# HSHV4-student_versionTester.net
KiCad netlist of a schematic drawn in EAGLE
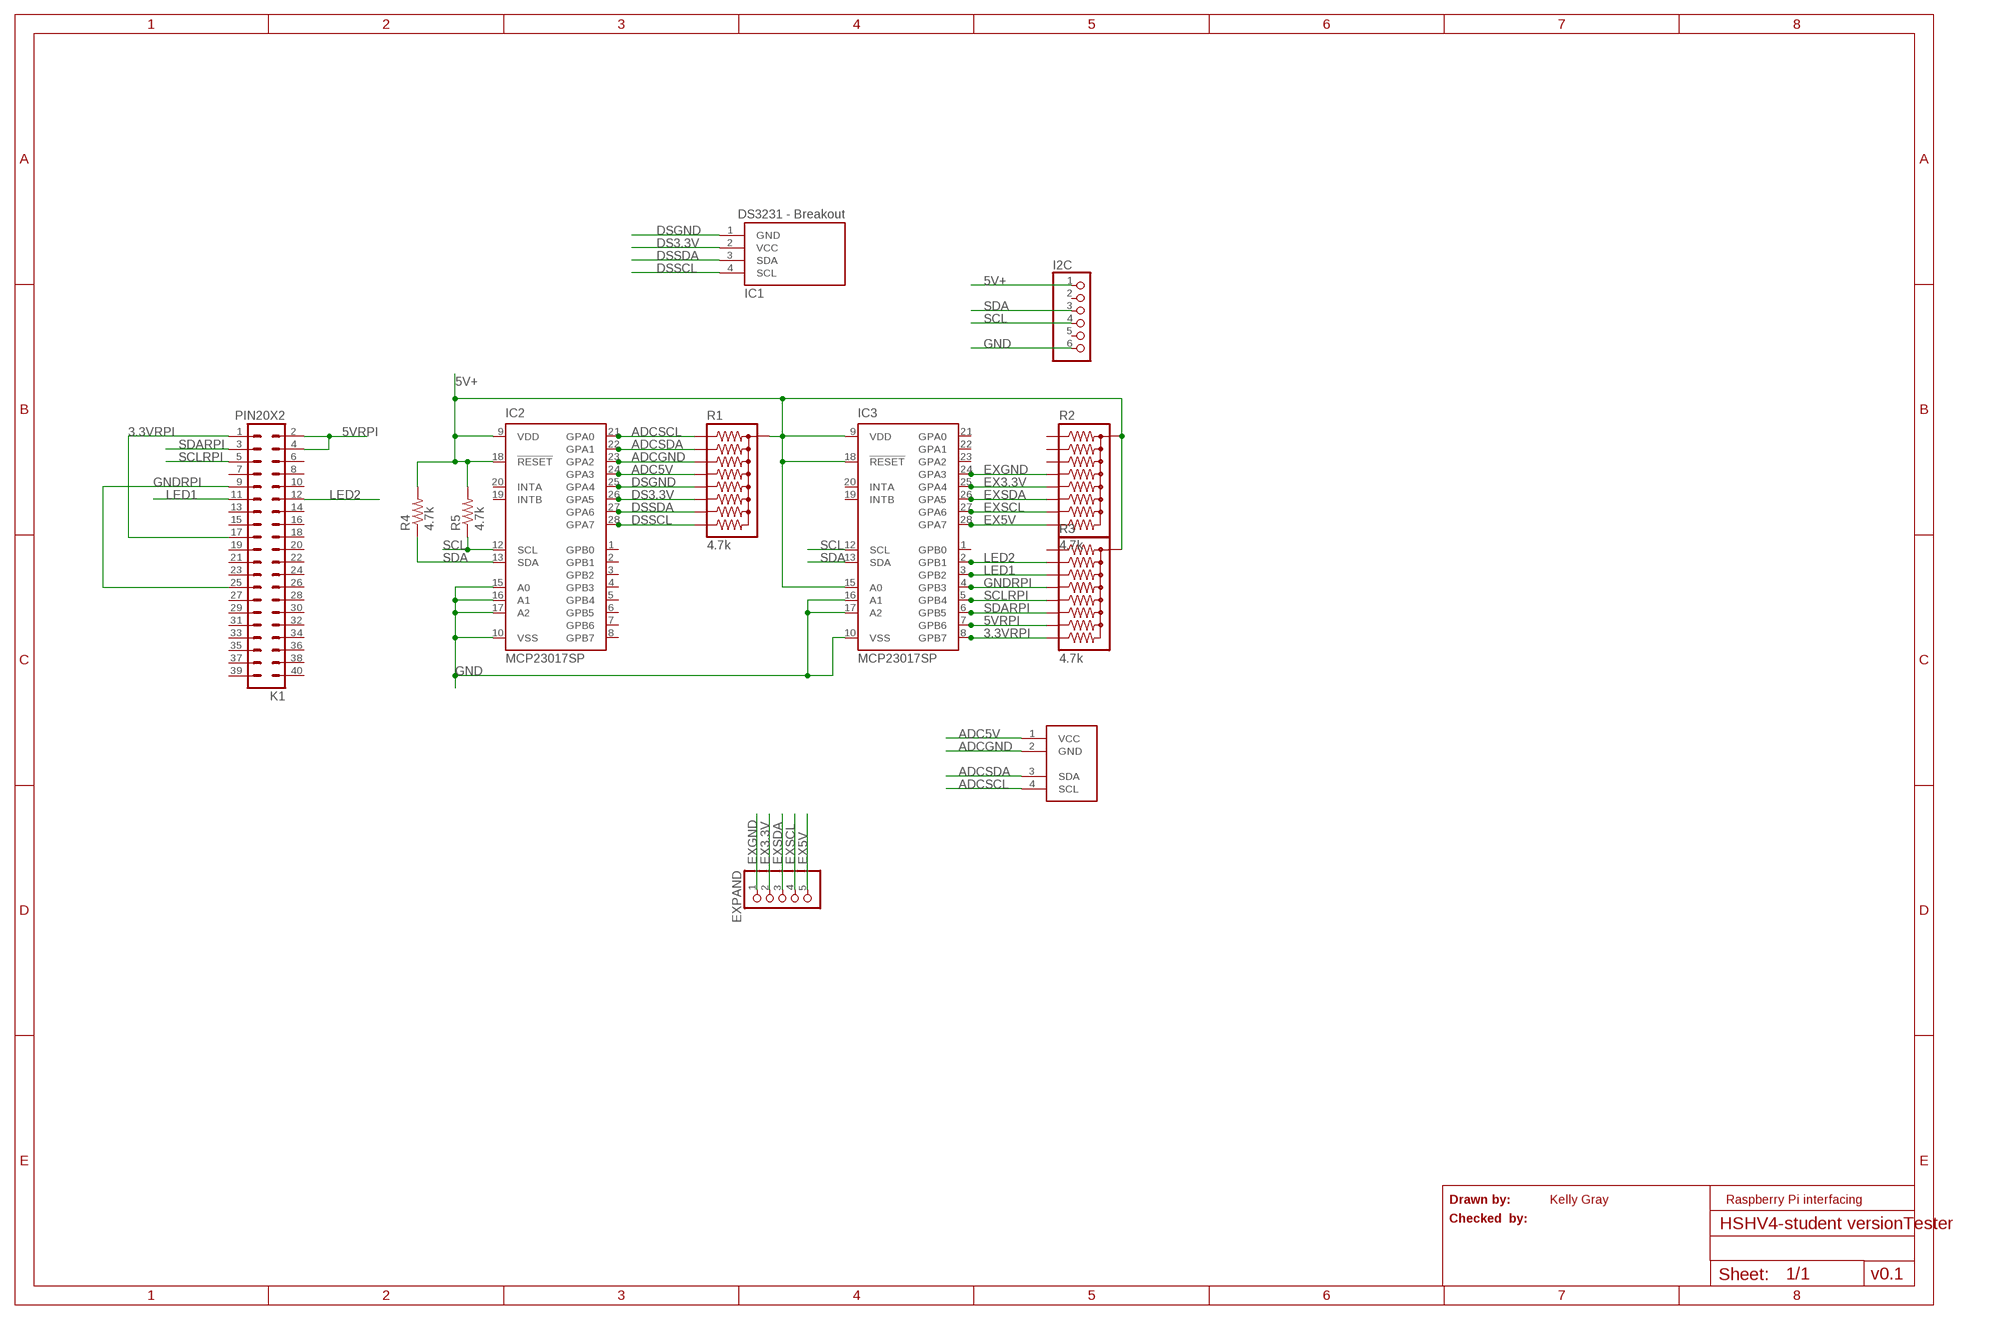
[diagram p0: schematic, sheet 1]

(export (version "E")
  (design (tool "Eeschema 10.0.6"))
  (components
    (comp (ref "EXPAND")
      (value "PINHD-1X5")
      (footprint "eagle-import:1X05")
      (libsource (lib "eagle-import") (part "PINHD-1X5"))
    )
    (comp (ref "I2C")
      (value "PINHD-1X6")
      (footprint "eagle-import:1X06")
      (libsource (lib "eagle-import") (part "PINHD-1X6"))
    )
    (comp (ref "IC1")
      (value "DS3231")
      (footprint "eagle-import:8PTH")
      (libsource (lib "eagle-import") (part "DS3231"))
    )
    (comp (ref "IC2")
      (value "MCP23017SP")
      (footprint "eagle-import:DIL28-3")
      (libsource (lib "eagle-import") (part "MCP23017SP"))
    )
    (comp (ref "IC3")
      (value "MCP23017SP")
      (footprint "eagle-import:DIL28-3")
      (libsource (lib "eagle-import") (part "MCP23017SP"))
    )
    (comp (ref "K1")
      (value "PIN20X2")
      (footprint "eagle-import:PIN_20X2")
      (libsource (lib "eagle-import") (part "PIN20X2"))
    )
    (comp (ref "R1")
      (value "4.7k")
      (footprint "eagle-import:RPACK-SIP-PTH-8")
      (libsource (lib "eagle-import") (part "RPACK-BUSSED-8-SIP-PTH-8"))
    )
    (comp (ref "R2")
      (value "4.7k")
      (footprint "eagle-import:RPACK-SIP-PTH-8")
      (libsource (lib "eagle-import") (part "RPACK-BUSSED-8-SIP-PTH-8"))
    )
    (comp (ref "R3")
      (value "4.7k")
      (footprint "eagle-import:RPACK-SIP-PTH-8")
      (libsource (lib "eagle-import") (part "RPACK-BUSSED-8-SIP-PTH-8"))
    )
    (comp (ref "R4")
      (value "4.7k")
      (footprint "eagle-import:0414_15")
      (libsource (lib "eagle-import") (part "R-US_0414/15"))
    )
    (comp (ref "R5")
      (value "4.7k")
      (footprint "eagle-import:0414_15")
      (libsource (lib "eagle-import") (part "R-US_0414/15"))
    )
    (comp (ref "U$1")
      (value "PCF8591")
      (footprint "eagle-import:1X04")
      (libsource (lib "eagle-import") (part "PCF8591"))
    )
  )
  (nets
    (net (code "1") (name "/3.3VRPI") (class "Default")
      (node (ref "IC3") (pin "8") (pinfunction "GPB7_8") (pintype "bidirectional"))
      (node (ref "K1") (pin "1") (pinfunction "1_1") (pintype "passive"))
      (node (ref "K1") (pin "17") (pinfunction "17_17") (pintype "passive"))
      (node (ref "R3") (pin "P$9") (pinfunction "9_P$9") (pintype "passive"))
    )
    (net (code "2") (name "/5V+") (class "Default")
      (node (ref "I2C") (pin "1") (pinfunction "1_1") (pintype "passive"))
      (node (ref "IC2") (pin "18") (pinfunction "~{RESET}_18") (pintype "input"))
      (node (ref "IC2") (pin "9") (pinfunction "VDD_9") (pintype "power_in"))
      (node (ref "IC3") (pin "15") (pinfunction "A0_15") (pintype "input"))
      (node (ref "IC3") (pin "18") (pinfunction "~{RESET}_18") (pintype "input"))
      (node (ref "IC3") (pin "9") (pinfunction "VDD_9") (pintype "power_in"))
      (node (ref "R1") (pin "P$1") (pinfunction "1_P$1") (pintype "passive"))
      (node (ref "R2") (pin "P$1") (pinfunction "1_P$1") (pintype "passive"))
      (node (ref "R3") (pin "P$1") (pinfunction "1_P$1") (pintype "passive"))
      (node (ref "R4") (pin "2") (pinfunction "2_2") (pintype "passive"))
      (node (ref "R5") (pin "2") (pinfunction "2_2") (pintype "passive"))
    )
    (net (code "3") (name "/5VRPI") (class "Default")
      (node (ref "IC3") (pin "7") (pinfunction "GPB6_7") (pintype "bidirectional"))
      (node (ref "K1") (pin "2") (pinfunction "2_2") (pintype "passive"))
      (node (ref "K1") (pin "4") (pinfunction "4_4") (pintype "passive"))
      (node (ref "R3") (pin "P$8") (pinfunction "8_P$8") (pintype "passive"))
    )
    (net (code "4") (name "/ADC5V") (class "Default")
      (node (ref "IC2") (pin "24") (pinfunction "GPA3_24") (pintype "bidirectional"))
      (node (ref "R1") (pin "P$5") (pinfunction "5_P$5") (pintype "passive"))
      (node (ref "U$1") (pin "1") (pinfunction "VCC_1") (pintype "bidirectional"))
    )
    (net (code "5") (name "/ADCGND") (class "Default")
      (node (ref "IC2") (pin "23") (pinfunction "GPA2_23") (pintype "bidirectional"))
      (node (ref "R1") (pin "P$4") (pinfunction "4_P$4") (pintype "passive"))
      (node (ref "U$1") (pin "2") (pinfunction "GND_2") (pintype "bidirectional"))
    )
    (net (code "6") (name "/ADCSCL") (class "Default")
      (node (ref "IC2") (pin "21") (pinfunction "GPA0_21") (pintype "bidirectional"))
      (node (ref "R1") (pin "P$2") (pinfunction "2_P$2") (pintype "passive"))
      (node (ref "U$1") (pin "4") (pinfunction "SCL_4") (pintype "bidirectional"))
    )
    (net (code "7") (name "/ADCSDA") (class "Default")
      (node (ref "IC2") (pin "22") (pinfunction "GPA1_22") (pintype "bidirectional"))
      (node (ref "R1") (pin "P$3") (pinfunction "3_P$3") (pintype "passive"))
      (node (ref "U$1") (pin "3") (pinfunction "SDA_3") (pintype "bidirectional"))
    )
    (net (code "8") (name "/DS3.3V") (class "Default")
      (node (ref "IC1") (pin "2") (pinfunction "VCC_2") (pintype "power_in"))
      (node (ref "IC2") (pin "26") (pinfunction "GPA5_26") (pintype "bidirectional"))
      (node (ref "R1") (pin "P$7") (pinfunction "7_P$7") (pintype "passive"))
    )
    (net (code "9") (name "/DSGND") (class "Default")
      (node (ref "IC1") (pin "1") (pinfunction "GND_1") (pintype "power_in"))
      (node (ref "IC2") (pin "25") (pinfunction "GPA4_25") (pintype "bidirectional"))
      (node (ref "R1") (pin "P$6") (pinfunction "6_P$6") (pintype "passive"))
    )
    (net (code "10") (name "/DSSCL") (class "Default")
      (node (ref "IC1") (pin "4") (pinfunction "SCL_4") (pintype "bidirectional"))
      (node (ref "IC2") (pin "28") (pinfunction "GPA7_28") (pintype "bidirectional"))
      (node (ref "R1") (pin "P$9") (pinfunction "9_P$9") (pintype "passive"))
    )
    (net (code "11") (name "/DSSDA") (class "Default")
      (node (ref "IC1") (pin "3") (pinfunction "SDA_3") (pintype "bidirectional"))
      (node (ref "IC2") (pin "27") (pinfunction "GPA6_27") (pintype "bidirectional"))
      (node (ref "R1") (pin "P$8") (pinfunction "8_P$8") (pintype "passive"))
    )
    (net (code "12") (name "/EX3.3V") (class "Default")
      (node (ref "EXPAND") (pin "2") (pinfunction "2_2") (pintype "passive"))
      (node (ref "IC3") (pin "25") (pinfunction "GPA4_25") (pintype "bidirectional"))
      (node (ref "R2") (pin "P$6") (pinfunction "6_P$6") (pintype "passive"))
    )
    (net (code "13") (name "/EX5V") (class "Default")
      (node (ref "EXPAND") (pin "5") (pinfunction "5_5") (pintype "passive"))
      (node (ref "IC3") (pin "28") (pinfunction "GPA7_28") (pintype "bidirectional"))
      (node (ref "R2") (pin "P$9") (pinfunction "9_P$9") (pintype "passive"))
    )
    (net (code "14") (name "/EXGND") (class "Default")
      (node (ref "EXPAND") (pin "1") (pinfunction "1_1") (pintype "passive"))
      (node (ref "IC3") (pin "24") (pinfunction "GPA3_24") (pintype "bidirectional"))
      (node (ref "R2") (pin "P$5") (pinfunction "5_P$5") (pintype "passive"))
    )
    (net (code "15") (name "/EXSCL") (class "Default")
      (node (ref "EXPAND") (pin "4") (pinfunction "4_4") (pintype "passive"))
      (node (ref "IC3") (pin "27") (pinfunction "GPA6_27") (pintype "bidirectional"))
      (node (ref "R2") (pin "P$8") (pinfunction "8_P$8") (pintype "passive"))
    )
    (net (code "16") (name "/EXSDA") (class "Default")
      (node (ref "EXPAND") (pin "3") (pinfunction "3_3") (pintype "passive"))
      (node (ref "IC3") (pin "26") (pinfunction "GPA5_26") (pintype "bidirectional"))
      (node (ref "R2") (pin "P$7") (pinfunction "7_P$7") (pintype "passive"))
    )
    (net (code "17") (name "/GND") (class "Default")
      (node (ref "I2C") (pin "6") (pinfunction "6_6") (pintype "passive"))
      (node (ref "IC2") (pin "10") (pinfunction "VSS_10") (pintype "power_in"))
      (node (ref "IC2") (pin "15") (pinfunction "A0_15") (pintype "input"))
      (node (ref "IC2") (pin "16") (pinfunction "A1_16") (pintype "input"))
      (node (ref "IC2") (pin "17") (pinfunction "A2_17") (pintype "input"))
      (node (ref "IC3") (pin "10") (pinfunction "VSS_10") (pintype "power_in"))
      (node (ref "IC3") (pin "16") (pinfunction "A1_16") (pintype "input"))
      (node (ref "IC3") (pin "17") (pinfunction "A2_17") (pintype "input"))
    )
    (net (code "18") (name "/GNDRPI") (class "Default")
      (node (ref "IC3") (pin "4") (pinfunction "GPB3_4") (pintype "bidirectional"))
      (node (ref "K1") (pin "25") (pinfunction "25_25") (pintype "passive"))
      (node (ref "K1") (pin "9") (pinfunction "9_9") (pintype "passive"))
      (node (ref "R3") (pin "P$5") (pinfunction "5_P$5") (pintype "passive"))
    )
    (net (code "19") (name "/LED1") (class "Default")
      (node (ref "IC3") (pin "3") (pinfunction "GPB2_3") (pintype "bidirectional"))
      (node (ref "K1") (pin "11") (pinfunction "11_11") (pintype "passive"))
      (node (ref "R3") (pin "P$4") (pinfunction "4_P$4") (pintype "passive"))
    )
    (net (code "20") (name "/LED2") (class "Default")
      (node (ref "IC3") (pin "2") (pinfunction "GPB1_2") (pintype "bidirectional"))
      (node (ref "K1") (pin "12") (pinfunction "12_12") (pintype "passive"))
      (node (ref "R3") (pin "P$3") (pinfunction "3_P$3") (pintype "passive"))
    )
    (net (code "21") (name "/SCL") (class "Default")
      (node (ref "I2C") (pin "4") (pinfunction "4_4") (pintype "passive"))
      (node (ref "IC2") (pin "12") (pinfunction "SCL_12") (pintype "input"))
      (node (ref "IC3") (pin "12") (pinfunction "SCL_12") (pintype "input"))
      (node (ref "R5") (pin "1") (pinfunction "1_1") (pintype "passive"))
    )
    (net (code "22") (name "/SCLRPI") (class "Default")
      (node (ref "IC3") (pin "5") (pinfunction "GPB4_5") (pintype "bidirectional"))
      (node (ref "K1") (pin "5") (pinfunction "5_5") (pintype "passive"))
      (node (ref "R3") (pin "P$6") (pinfunction "6_P$6") (pintype "passive"))
    )
    (net (code "23") (name "/SDA") (class "Default")
      (node (ref "I2C") (pin "3") (pinfunction "3_3") (pintype "passive"))
      (node (ref "IC2") (pin "13") (pinfunction "SDA_13") (pintype "bidirectional"))
      (node (ref "IC3") (pin "13") (pinfunction "SDA_13") (pintype "bidirectional"))
      (node (ref "R4") (pin "1") (pinfunction "1_1") (pintype "passive"))
    )
    (net (code "24") (name "/SDARPI") (class "Default")
      (node (ref "IC3") (pin "6") (pinfunction "GPB5_6") (pintype "bidirectional"))
      (node (ref "K1") (pin "3") (pinfunction "3_3") (pintype "passive"))
      (node (ref "R3") (pin "P$7") (pinfunction "7_P$7") (pintype "passive"))
    )
    (net (code "25") (name "unconnected-(I2C-Pad2)") (class "Default")
      (node (ref "I2C") (pin "2") (pinfunction "2_2") (pintype "passive"))
    )
    (net (code "26") (name "unconnected-(I2C-Pad5)") (class "Default")
      (node (ref "I2C") (pin "5") (pinfunction "5_5") (pintype "passive"))
    )
    (net (code "27") (name "unconnected-(IC2-GPB0-Pad1)") (class "Default")
      (node (ref "IC2") (pin "1") (pinfunction "GPB0_1") (pintype "bidirectional"))
    )
    (net (code "28") (name "unconnected-(IC2-GPB1-Pad2)") (class "Default")
      (node (ref "IC2") (pin "2") (pinfunction "GPB1_2") (pintype "bidirectional"))
    )
    (net (code "29") (name "unconnected-(IC2-GPB2-Pad3)") (class "Default")
      (node (ref "IC2") (pin "3") (pinfunction "GPB2_3") (pintype "bidirectional"))
    )
    (net (code "30") (name "unconnected-(IC2-GPB3-Pad4)") (class "Default")
      (node (ref "IC2") (pin "4") (pinfunction "GPB3_4") (pintype "bidirectional"))
    )
    (net (code "31") (name "unconnected-(IC2-GPB4-Pad5)") (class "Default")
      (node (ref "IC2") (pin "5") (pinfunction "GPB4_5") (pintype "bidirectional"))
    )
    (net (code "32") (name "unconnected-(IC2-GPB5-Pad6)") (class "Default")
      (node (ref "IC2") (pin "6") (pinfunction "GPB5_6") (pintype "bidirectional"))
    )
    (net (code "33") (name "unconnected-(IC2-GPB6-Pad7)") (class "Default")
      (node (ref "IC2") (pin "7") (pinfunction "GPB6_7") (pintype "bidirectional"))
    )
    (net (code "34") (name "unconnected-(IC2-GPB7-Pad8)") (class "Default")
      (node (ref "IC2") (pin "8") (pinfunction "GPB7_8") (pintype "bidirectional"))
    )
    (net (code "35") (name "unconnected-(IC2-INTA-Pad20)") (class "Default")
      (node (ref "IC2") (pin "20") (pinfunction "INTA_20") (pintype "output"))
    )
    (net (code "36") (name "unconnected-(IC2-INTB-Pad19)") (class "Default")
      (node (ref "IC2") (pin "19") (pinfunction "INTB_19") (pintype "output"))
    )
    (net (code "37") (name "unconnected-(IC3-GPA0-Pad21)") (class "Default")
      (node (ref "IC3") (pin "21") (pinfunction "GPA0_21") (pintype "bidirectional"))
    )
    (net (code "38") (name "unconnected-(IC3-GPA1-Pad22)") (class "Default")
      (node (ref "IC3") (pin "22") (pinfunction "GPA1_22") (pintype "bidirectional"))
    )
    (net (code "39") (name "unconnected-(IC3-GPA2-Pad23)") (class "Default")
      (node (ref "IC3") (pin "23") (pinfunction "GPA2_23") (pintype "bidirectional"))
    )
    (net (code "40") (name "unconnected-(IC3-GPB0-Pad1)") (class "Default")
      (node (ref "IC3") (pin "1") (pinfunction "GPB0_1") (pintype "bidirectional"))
    )
    (net (code "41") (name "unconnected-(IC3-INTA-Pad20)") (class "Default")
      (node (ref "IC3") (pin "20") (pinfunction "INTA_20") (pintype "output"))
    )
    (net (code "42") (name "unconnected-(IC3-INTB-Pad19)") (class "Default")
      (node (ref "IC3") (pin "19") (pinfunction "INTB_19") (pintype "output"))
    )
    (net (code "43") (name "unconnected-(K1-Pad6)") (class "Default")
      (node (ref "K1") (pin "6") (pinfunction "6_6") (pintype "passive"))
    )
    (net (code "44") (name "unconnected-(K1-Pad7)") (class "Default")
      (node (ref "K1") (pin "7") (pinfunction "7_7") (pintype "passive"))
    )
    (net (code "45") (name "unconnected-(K1-Pad8)") (class "Default")
      (node (ref "K1") (pin "8") (pinfunction "8_8") (pintype "passive"))
    )
    (net (code "46") (name "unconnected-(K1-Pad10)") (class "Default")
      (node (ref "K1") (pin "10") (pinfunction "10_10") (pintype "passive"))
    )
    (net (code "47") (name "unconnected-(K1-Pad13)") (class "Default")
      (node (ref "K1") (pin "13") (pinfunction "13_13") (pintype "passive"))
    )
    (net (code "48") (name "unconnected-(K1-Pad14)") (class "Default")
      (node (ref "K1") (pin "14") (pinfunction "14_14") (pintype "passive"))
    )
    (net (code "49") (name "unconnected-(K1-Pad15)") (class "Default")
      (node (ref "K1") (pin "15") (pinfunction "15_15") (pintype "passive"))
    )
    (net (code "50") (name "unconnected-(K1-Pad16)") (class "Default")
      (node (ref "K1") (pin "16") (pinfunction "16_16") (pintype "passive"))
    )
    (net (code "51") (name "unconnected-(K1-Pad18)") (class "Default")
      (node (ref "K1") (pin "18") (pinfunction "18_18") (pintype "passive"))
    )
    (net (code "52") (name "unconnected-(K1-Pad19)") (class "Default")
      (node (ref "K1") (pin "19") (pinfunction "19_19") (pintype "passive"))
    )
    (net (code "53") (name "unconnected-(K1-Pad20)") (class "Default")
      (node (ref "K1") (pin "20") (pinfunction "20_20") (pintype "passive"))
    )
    (net (code "54") (name "unconnected-(K1-Pad21)") (class "Default")
      (node (ref "K1") (pin "21") (pinfunction "21_21") (pintype "passive"))
    )
    (net (code "55") (name "unconnected-(K1-Pad22)") (class "Default")
      (node (ref "K1") (pin "22") (pinfunction "22_22") (pintype "passive"))
    )
    (net (code "56") (name "unconnected-(K1-Pad23)") (class "Default")
      (node (ref "K1") (pin "23") (pinfunction "23_23") (pintype "passive"))
    )
    (net (code "57") (name "unconnected-(K1-Pad24)") (class "Default")
      (node (ref "K1") (pin "24") (pinfunction "24_24") (pintype "passive"))
    )
    (net (code "58") (name "unconnected-(K1-Pad26)") (class "Default")
      (node (ref "K1") (pin "26") (pinfunction "26_26") (pintype "passive"))
    )
    (net (code "59") (name "unconnected-(K1-Pad27)") (class "Default")
      (node (ref "K1") (pin "27") (pinfunction "27_27") (pintype "passive"))
    )
    (net (code "60") (name "unconnected-(K1-Pad28)") (class "Default")
      (node (ref "K1") (pin "28") (pinfunction "28_28") (pintype "passive"))
    )
    (net (code "61") (name "unconnected-(K1-Pad29)") (class "Default")
      (node (ref "K1") (pin "29") (pinfunction "29_29") (pintype "passive"))
    )
    (net (code "62") (name "unconnected-(K1-Pad30)") (class "Default")
      (node (ref "K1") (pin "30") (pinfunction "30_30") (pintype "passive"))
    )
    (net (code "63") (name "unconnected-(K1-Pad31)") (class "Default")
      (node (ref "K1") (pin "31") (pinfunction "31_31") (pintype "passive"))
    )
    (net (code "64") (name "unconnected-(K1-Pad32)") (class "Default")
      (node (ref "K1") (pin "32") (pinfunction "32_32") (pintype "passive"))
    )
    (net (code "65") (name "unconnected-(K1-Pad33)") (class "Default")
      (node (ref "K1") (pin "33") (pinfunction "33_33") (pintype "passive"))
    )
    (net (code "66") (name "unconnected-(K1-Pad34)") (class "Default")
      (node (ref "K1") (pin "34") (pinfunction "34_34") (pintype "passive"))
    )
    (net (code "67") (name "unconnected-(K1-Pad35)") (class "Default")
      (node (ref "K1") (pin "35") (pinfunction "35_35") (pintype "passive"))
    )
    (net (code "68") (name "unconnected-(K1-Pad36)") (class "Default")
      (node (ref "K1") (pin "36") (pinfunction "36_36") (pintype "passive"))
    )
    (net (code "69") (name "unconnected-(K1-Pad37)") (class "Default")
      (node (ref "K1") (pin "37") (pinfunction "37_37") (pintype "passive"))
    )
    (net (code "70") (name "unconnected-(K1-Pad38)") (class "Default")
      (node (ref "K1") (pin "38") (pinfunction "38_38") (pintype "passive"))
    )
    (net (code "71") (name "unconnected-(K1-Pad39)") (class "Default")
      (node (ref "K1") (pin "39") (pinfunction "39_39") (pintype "passive"))
    )
    (net (code "72") (name "unconnected-(K1-Pad40)") (class "Default")
      (node (ref "K1") (pin "40") (pinfunction "40_40") (pintype "passive"))
    )
    (net (code "73") (name "unconnected-(R2-2-PadP$2)") (class "Default")
      (node (ref "R2") (pin "P$2") (pinfunction "2_P$2") (pintype "passive"))
    )
    (net (code "74") (name "unconnected-(R2-3-PadP$3)") (class "Default")
      (node (ref "R2") (pin "P$3") (pinfunction "3_P$3") (pintype "passive"))
    )
    (net (code "75") (name "unconnected-(R2-4-PadP$4)") (class "Default")
      (node (ref "R2") (pin "P$4") (pinfunction "4_P$4") (pintype "passive"))
    )
    (net (code "76") (name "unconnected-(R3-2-PadP$2)") (class "Default")
      (node (ref "R3") (pin "P$2") (pinfunction "2_P$2") (pintype "passive"))
    )
  )
)
